# CC-S02-V00-HighSideOutputs.net
KiCad netlist of a schematic drawn in Altium Designer
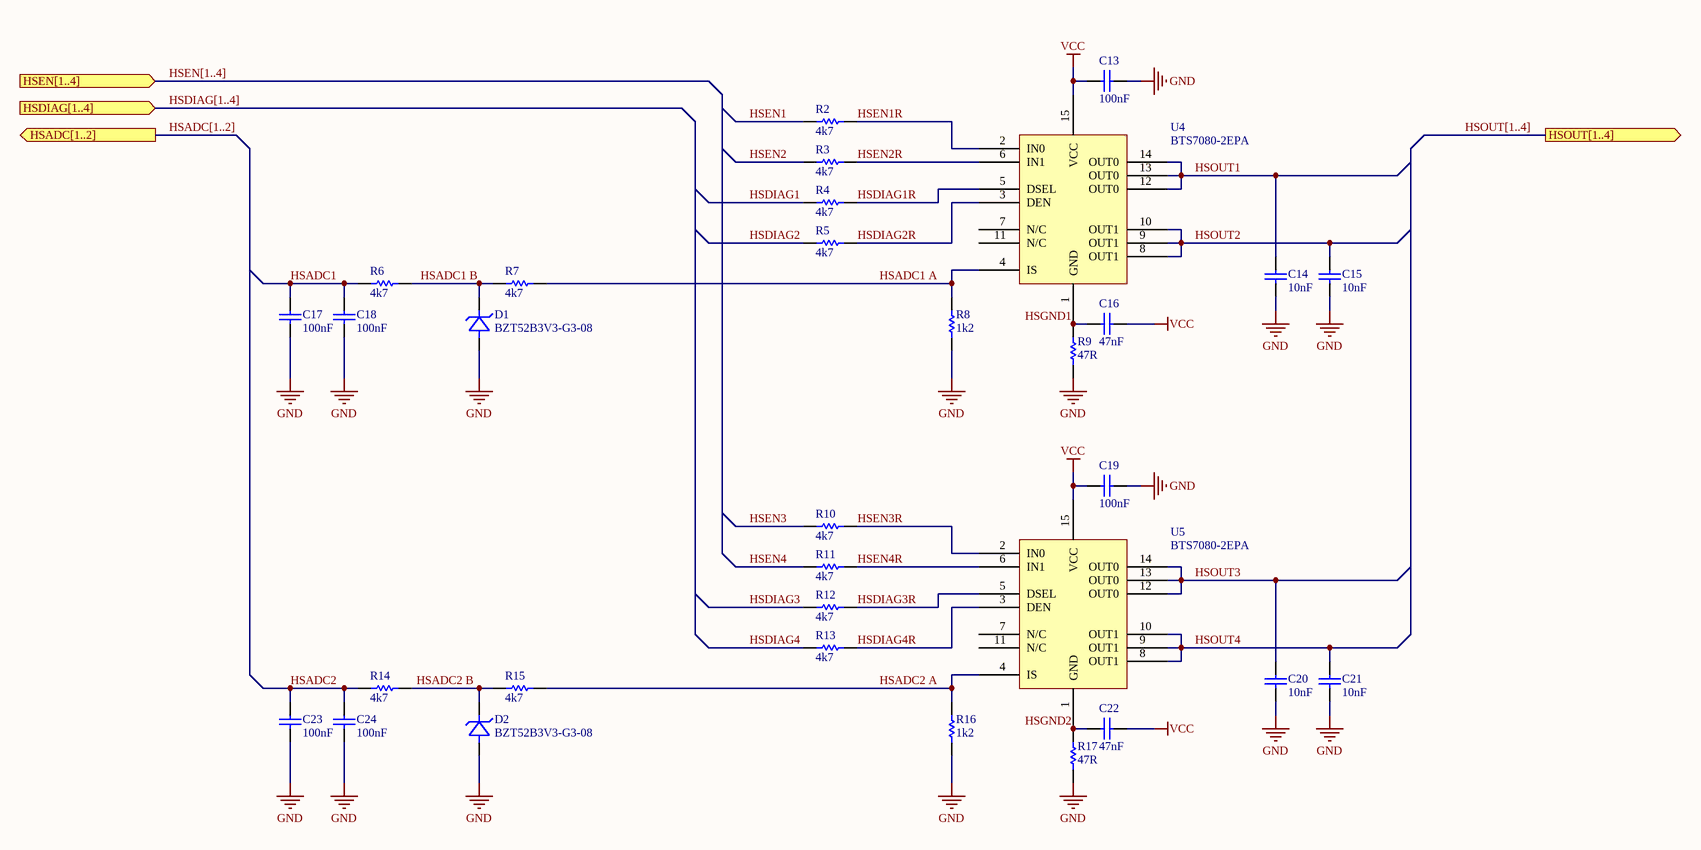
[diagram p0: CC-S02-V00-HighSideOutputs.SchDoc]

(export (version "E")
  (design (tool "Eeschema 10.0.6"))
  (components
    (comp (ref "C13")
      (value "100nF")
      (footprint "Cap_Ceramic_0603")
      (description "Capacitor, Ceramic, SMD, 100nF, 50V, 5%, X7R, 0603")
      (libsource (lib "StandardCapacitors") (part "100nF 50V 5% X7R 0603"))
    )
    (comp (ref "C14")
      (value "10nF")
      (footprint "Cap_Ceramic_0603")
      (description "Capacitor, Ceramic, SMD, 10nF, 50V, 5%, X7R, 0603")
      (libsource (lib "StandardCapacitors") (part "10nF 50V 5% X7R 0603"))
    )
    (comp (ref "C15")
      (value "10nF")
      (footprint "Cap_Ceramic_0603")
      (description "Capacitor, Ceramic, SMD, 10nF, 50V, 5%, X7R, 0603")
      (libsource (lib "StandardCapacitors") (part "10nF 50V 5% X7R 0603"))
    )
    (comp (ref "C16")
      (value "47nF")
      (footprint "Cap_Ceramic_0603")
      (description "Capacitor, Ceramic, SMD, 47nF, 50V, 5%, X7R, 0603")
      (libsource (lib "StandardCapacitors") (part "47nF 50V 5% X7R 0603"))
    )
    (comp (ref "C17")
      (value "100nF")
      (footprint "Cap_Ceramic_0603")
      (description "Capacitor, Ceramic, SMD, 100nF, 50V, 5%, X7R, 0603")
      (libsource (lib "StandardCapacitors") (part "100nF 50V 5% X7R 0603"))
    )
    (comp (ref "C18")
      (value "100nF")
      (footprint "Cap_Ceramic_0603")
      (description "Capacitor, Ceramic, SMD, 100nF, 50V, 5%, X7R, 0603")
      (libsource (lib "StandardCapacitors") (part "100nF 50V 5% X7R 0603"))
    )
    (comp (ref "C19")
      (value "100nF")
      (footprint "Cap_Ceramic_0603")
      (description "Capacitor, Ceramic, SMD, 100nF, 50V, 5%, X7R, 0603")
      (libsource (lib "StandardCapacitors") (part "100nF 50V 5% X7R 0603"))
    )
    (comp (ref "C20")
      (value "10nF")
      (footprint "Cap_Ceramic_0603")
      (description "Capacitor, Ceramic, SMD, 10nF, 50V, 5%, X7R, 0603")
      (libsource (lib "StandardCapacitors") (part "10nF 50V 5% X7R 0603"))
    )
    (comp (ref "C21")
      (value "10nF")
      (footprint "Cap_Ceramic_0603")
      (description "Capacitor, Ceramic, SMD, 10nF, 50V, 5%, X7R, 0603")
      (libsource (lib "StandardCapacitors") (part "10nF 50V 5% X7R 0603"))
    )
    (comp (ref "C22")
      (value "47nF")
      (footprint "Cap_Ceramic_0603")
      (description "Capacitor, Ceramic, SMD, 47nF, 50V, 5%, X7R, 0603")
      (libsource (lib "StandardCapacitors") (part "47nF 50V 5% X7R 0603"))
    )
    (comp (ref "C23")
      (value "100nF")
      (footprint "Cap_Ceramic_0603")
      (description "Capacitor, Ceramic, SMD, 100nF, 50V, 5%, X7R, 0603")
      (libsource (lib "StandardCapacitors") (part "100nF 50V 5% X7R 0603"))
    )
    (comp (ref "C24")
      (value "100nF")
      (footprint "Cap_Ceramic_0603")
      (description "Capacitor, Ceramic, SMD, 100nF, 50V, 5%, X7R, 0603")
      (libsource (lib "StandardCapacitors") (part "100nF 50V 5% X7R 0603"))
    )
    (comp (ref "D1")
      (value "BZT52B3V3-G3-08")
      (footprint "SOD123")
      (description "Diode, SMD, Zenner, 3.3V, 2%, 410mW, SOD-123")
      (libsource (lib "QUTMS_DiodeLibrary") (part "BZT52B3V3-G3-08"))
    )
    (comp (ref "D2")
      (value "BZT52B3V3-G3-08")
      (footprint "SOD123")
      (description "Diode, SMD, Zenner, 3.3V, 2%, 410mW, SOD-123")
      (libsource (lib "QUTMS_DiodeLibrary") (part "BZT52B3V3-G3-08"))
    )
    (comp (ref "R2")
      (value "4k7")
      (footprint "Res_ThinFilm_0603")
      (description "Resistor, SMD, 4k7, 0.1W, 5%, 0603")
      (libsource (lib "StandardResistors") (part "4k7 5% 0603"))
    )
    (comp (ref "R3")
      (value "4k7")
      (footprint "Res_ThinFilm_0603")
      (description "Resistor, SMD, 4k7, 0.1W, 5%, 0603")
      (libsource (lib "StandardResistors") (part "4k7 5% 0603"))
    )
    (comp (ref "R4")
      (value "4k7")
      (footprint "Res_ThinFilm_0603")
      (description "Resistor, SMD, 4k7, 0.1W, 5%, 0603")
      (libsource (lib "StandardResistors") (part "4k7 5% 0603"))
    )
    (comp (ref "R5")
      (value "4k7")
      (footprint "Res_ThinFilm_0603")
      (description "Resistor, SMD, 4k7, 0.1W, 5%, 0603")
      (libsource (lib "StandardResistors") (part "4k7 5% 0603"))
    )
    (comp (ref "R6")
      (value "4k7")
      (footprint "Res_ThinFilm_0603")
      (description "Resistor, SMD, 4k7, 0.1W, 5%, 0603")
      (libsource (lib "StandardResistors") (part "4k7 5% 0603"))
    )
    (comp (ref "R7")
      (value "4k7")
      (footprint "Res_ThinFilm_0603")
      (description "Resistor, SMD, 4k7, 0.1W, 5%, 0603")
      (libsource (lib "StandardResistors") (part "4k7 5% 0603"))
    )
    (comp (ref "R8")
      (value "1k2")
      (footprint "Res_ThinFilm_0603")
      (description "Resistor, SMD, 1k2, 0.1W, 5%, 0603")
      (libsource (lib "StandardResistors") (part "1k2 5% 0603"))
    )
    (comp (ref "R9")
      (value "47R")
      (footprint "Res_ThinFilm_0603")
      (description "Resistor, SMD, 47R, 0.1W, 5%, 0603")
      (libsource (lib "StandardResistors") (part "47R 5% 0603"))
    )
    (comp (ref "R10")
      (value "4k7")
      (footprint "Res_ThinFilm_0603")
      (description "Resistor, SMD, 4k7, 0.1W, 5%, 0603")
      (libsource (lib "StandardResistors") (part "4k7 5% 0603"))
    )
    (comp (ref "R11")
      (value "4k7")
      (footprint "Res_ThinFilm_0603")
      (description "Resistor, SMD, 4k7, 0.1W, 5%, 0603")
      (libsource (lib "StandardResistors") (part "4k7 5% 0603"))
    )
    (comp (ref "R12")
      (value "4k7")
      (footprint "Res_ThinFilm_0603")
      (description "Resistor, SMD, 4k7, 0.1W, 5%, 0603")
      (libsource (lib "StandardResistors") (part "4k7 5% 0603"))
    )
    (comp (ref "R13")
      (value "4k7")
      (footprint "Res_ThinFilm_0603")
      (description "Resistor, SMD, 4k7, 0.1W, 5%, 0603")
      (libsource (lib "StandardResistors") (part "4k7 5% 0603"))
    )
    (comp (ref "R14")
      (value "4k7")
      (footprint "Res_ThinFilm_0603")
      (description "Resistor, SMD, 4k7, 0.1W, 5%, 0603")
      (libsource (lib "StandardResistors") (part "4k7 5% 0603"))
    )
    (comp (ref "R15")
      (value "4k7")
      (footprint "Res_ThinFilm_0603")
      (description "Resistor, SMD, 4k7, 0.1W, 5%, 0603")
      (libsource (lib "StandardResistors") (part "4k7 5% 0603"))
    )
    (comp (ref "R16")
      (value "1k2")
      (footprint "Res_ThinFilm_0603")
      (description "Resistor, SMD, 1k2, 0.1W, 5%, 0603")
      (libsource (lib "StandardResistors") (part "1k2 5% 0603"))
    )
    (comp (ref "R17")
      (value "47R")
      (footprint "Res_ThinFilm_0603")
      (description "Resistor, SMD, 47R, 0.1W, 5%, 0603")
      (libsource (lib "StandardResistors") (part "47R 5% 0603"))
    )
    (comp (ref "U4")
      (value "BTS7080-2EPA")
      (footprint "BTS70802EPA")
      (description "Power Switch/Driver 1:1 N-Channel 3A PG-TSDSO-14-22")
      (libsource (lib "QUTMS_MOSFETLibrary") (part "BTS7080-2EPA"))
    )
    (comp (ref "U5")
      (value "BTS7080-2EPA")
      (footprint "BTS70802EPA")
      (description "Power Switch/Driver 1:1 N-Channel 3A PG-TSDSO-14-22")
      (libsource (lib "QUTMS_MOSFETLibrary") (part "BTS7080-2EPA"))
    )
  )
  (nets
    (net (code "1") (name "/HSADC1") (class "Default")
      (node (ref "C17") (pin "2") (pinfunction "2_2") (pintype "passive"))
      (node (ref "C18") (pin "2") (pinfunction "2_2") (pintype "passive"))
      (node (ref "R6") (pin "1") (pinfunction "1_1") (pintype "passive"))
    )
    (net (code "2") (name "/HSADC1 A") (class "Default")
      (node (ref "R7") (pin "2") (pinfunction "2_2") (pintype "passive"))
      (node (ref "R8") (pin "1") (pinfunction "1_1") (pintype "passive"))
      (node (ref "U4") (pin "4") (pinfunction "IS_4") (pintype "passive"))
    )
    (net (code "3") (name "/HSADC1 B") (class "Default")
      (node (ref "D1") (pin "K") (pinfunction "Cathode_K") (pintype "passive"))
      (node (ref "R6") (pin "2") (pinfunction "2_2") (pintype "passive"))
      (node (ref "R7") (pin "1") (pinfunction "1_1") (pintype "passive"))
    )
    (net (code "4") (name "/HSADC2") (class "Default")
      (node (ref "C23") (pin "2") (pinfunction "2_2") (pintype "passive"))
      (node (ref "C24") (pin "2") (pinfunction "2_2") (pintype "passive"))
      (node (ref "R14") (pin "1") (pinfunction "1_1") (pintype "passive"))
    )
    (net (code "5") (name "/HSADC2 A") (class "Default")
      (node (ref "R15") (pin "2") (pinfunction "2_2") (pintype "passive"))
      (node (ref "R16") (pin "1") (pinfunction "1_1") (pintype "passive"))
      (node (ref "U5") (pin "4") (pinfunction "IS_4") (pintype "passive"))
    )
    (net (code "6") (name "/HSADC2 B") (class "Default")
      (node (ref "D2") (pin "K") (pinfunction "Cathode_K") (pintype "passive"))
      (node (ref "R14") (pin "2") (pinfunction "2_2") (pintype "passive"))
      (node (ref "R15") (pin "1") (pinfunction "1_1") (pintype "passive"))
    )
    (net (code "8") (name "/HSDIAG1") (class "Default")
      (node (ref "R4") (pin "1") (pinfunction "1_1") (pintype "passive"))
    )
    (net (code "9") (name "/HSDIAG1R") (class "Default")
      (node (ref "R4") (pin "2") (pinfunction "2_2") (pintype "passive"))
      (node (ref "U4") (pin "5") (pinfunction "DSEL_5") (pintype "passive"))
    )
    (net (code "10") (name "/HSDIAG2") (class "Default")
      (node (ref "R5") (pin "1") (pinfunction "1_1") (pintype "passive"))
    )
    (net (code "11") (name "/HSDIAG2R") (class "Default")
      (node (ref "R5") (pin "2") (pinfunction "2_2") (pintype "passive"))
      (node (ref "U4") (pin "3") (pinfunction "DEN_3") (pintype "passive"))
    )
    (net (code "12") (name "/HSDIAG3") (class "Default")
      (node (ref "R12") (pin "1") (pinfunction "1_1") (pintype "passive"))
    )
    (net (code "13") (name "/HSDIAG3R") (class "Default")
      (node (ref "R12") (pin "2") (pinfunction "2_2") (pintype "passive"))
      (node (ref "U5") (pin "5") (pinfunction "DSEL_5") (pintype "passive"))
    )
    (net (code "14") (name "/HSDIAG4") (class "Default")
      (node (ref "R13") (pin "1") (pinfunction "1_1") (pintype "passive"))
    )
    (net (code "15") (name "/HSDIAG4R") (class "Default")
      (node (ref "R13") (pin "2") (pinfunction "2_2") (pintype "passive"))
      (node (ref "U5") (pin "3") (pinfunction "DEN_3") (pintype "passive"))
    )
    (net (code "17") (name "/HSEN1") (class "Default")
      (node (ref "R2") (pin "1") (pinfunction "1_1") (pintype "passive"))
    )
    (net (code "18") (name "/HSEN1R") (class "Default")
      (node (ref "R2") (pin "2") (pinfunction "2_2") (pintype "passive"))
      (node (ref "U4") (pin "2") (pinfunction "IN0_2") (pintype "passive"))
    )
    (net (code "19") (name "/HSEN2") (class "Default")
      (node (ref "R3") (pin "1") (pinfunction "1_1") (pintype "passive"))
    )
    (net (code "20") (name "/HSEN2R") (class "Default")
      (node (ref "R3") (pin "2") (pinfunction "2_2") (pintype "passive"))
      (node (ref "U4") (pin "6") (pinfunction "IN1_6") (pintype "passive"))
    )
    (net (code "21") (name "/HSEN3") (class "Default")
      (node (ref "R10") (pin "1") (pinfunction "1_1") (pintype "passive"))
    )
    (net (code "22") (name "/HSEN3R") (class "Default")
      (node (ref "R10") (pin "2") (pinfunction "2_2") (pintype "passive"))
      (node (ref "U5") (pin "2") (pinfunction "IN0_2") (pintype "passive"))
    )
    (net (code "23") (name "/HSEN4") (class "Default")
      (node (ref "R11") (pin "1") (pinfunction "1_1") (pintype "passive"))
    )
    (net (code "24") (name "/HSEN4R") (class "Default")
      (node (ref "R11") (pin "2") (pinfunction "2_2") (pintype "passive"))
      (node (ref "U5") (pin "6") (pinfunction "IN1_6") (pintype "passive"))
    )
    (net (code "26") (name "/HSGND1") (class "Default")
      (node (ref "C16") (pin "1") (pinfunction "1_1") (pintype "passive"))
      (node (ref "R9") (pin "2") (pinfunction "2_2") (pintype "passive"))
      (node (ref "U4") (pin "1") (pinfunction "GND_1") (pintype "passive"))
    )
    (net (code "27") (name "/HSGND2") (class "Default")
      (node (ref "C22") (pin "1") (pinfunction "1_1") (pintype "passive"))
      (node (ref "R17") (pin "2") (pinfunction "2_2") (pintype "passive"))
      (node (ref "U5") (pin "1") (pinfunction "GND_1") (pintype "passive"))
    )
    (net (code "28") (name "/HSOUT1") (class "Default")
      (node (ref "C14") (pin "2") (pinfunction "2_2") (pintype "passive"))
      (node (ref "U4") (pin "12") (pinfunction "OUT0_12") (pintype "passive"))
      (node (ref "U4") (pin "13") (pinfunction "OUT0_13") (pintype "passive"))
      (node (ref "U4") (pin "14") (pinfunction "OUT0_14") (pintype "passive"))
    )
    (net (code "29") (name "/HSOUT2") (class "Default")
      (node (ref "C15") (pin "2") (pinfunction "2_2") (pintype "passive"))
      (node (ref "U4") (pin "10") (pinfunction "OUT1_10") (pintype "passive"))
      (node (ref "U4") (pin "8") (pinfunction "OUT1_8") (pintype "passive"))
      (node (ref "U4") (pin "9") (pinfunction "OUT1_9") (pintype "passive"))
    )
    (net (code "30") (name "/HSOUT3") (class "Default")
      (node (ref "C20") (pin "2") (pinfunction "2_2") (pintype "passive"))
      (node (ref "U5") (pin "12") (pinfunction "OUT0_12") (pintype "passive"))
      (node (ref "U5") (pin "13") (pinfunction "OUT0_13") (pintype "passive"))
      (node (ref "U5") (pin "14") (pinfunction "OUT0_14") (pintype "passive"))
    )
    (net (code "31") (name "/HSOUT4") (class "Default")
      (node (ref "C21") (pin "2") (pinfunction "2_2") (pintype "passive"))
      (node (ref "U5") (pin "10") (pinfunction "OUT1_10") (pintype "passive"))
      (node (ref "U5") (pin "8") (pinfunction "OUT1_8") (pintype "passive"))
      (node (ref "U5") (pin "9") (pinfunction "OUT1_9") (pintype "passive"))
    )
    (net (code "33") (name "GND") (class "Default")
      (node (ref "C13") (pin "2") (pinfunction "2_2") (pintype "passive"))
      (node (ref "C14") (pin "1") (pinfunction "1_1") (pintype "passive"))
      (node (ref "C15") (pin "1") (pinfunction "1_1") (pintype "passive"))
      (node (ref "C17") (pin "1") (pinfunction "1_1") (pintype "passive"))
      (node (ref "C18") (pin "1") (pinfunction "1_1") (pintype "passive"))
      (node (ref "C19") (pin "2") (pinfunction "2_2") (pintype "passive"))
      (node (ref "C20") (pin "1") (pinfunction "1_1") (pintype "passive"))
      (node (ref "C21") (pin "1") (pinfunction "1_1") (pintype "passive"))
      (node (ref "C23") (pin "1") (pinfunction "1_1") (pintype "passive"))
      (node (ref "C24") (pin "1") (pinfunction "1_1") (pintype "passive"))
      (node (ref "D1") (pin "A") (pinfunction "Anode_A") (pintype "passive"))
      (node (ref "D2") (pin "A") (pinfunction "Anode_A") (pintype "passive"))
      (node (ref "R16") (pin "2") (pinfunction "2_2") (pintype "passive"))
      (node (ref "R17") (pin "1") (pinfunction "1_1") (pintype "passive"))
      (node (ref "R8") (pin "2") (pinfunction "2_2") (pintype "passive"))
      (node (ref "R9") (pin "1") (pinfunction "1_1") (pintype "passive"))
    )
    (net (code "34") (name "VCC") (class "Default")
      (node (ref "C13") (pin "1") (pinfunction "1_1") (pintype "passive"))
      (node (ref "C16") (pin "2") (pinfunction "2_2") (pintype "passive"))
      (node (ref "C19") (pin "1") (pinfunction "1_1") (pintype "passive"))
      (node (ref "C22") (pin "2") (pinfunction "2_2") (pintype "passive"))
      (node (ref "U4") (pin "15") (pinfunction "VCC_15") (pintype "passive"))
      (node (ref "U5") (pin "15") (pinfunction "VCC_15") (pintype "passive"))
    )
    (net (code "35") (name "unconnected-(U4-N{slash}C-Pad7)") (class "Default")
      (node (ref "U4") (pin "7") (pinfunction "N/C_7") (pintype "passive"))
    )
    (net (code "36") (name "unconnected-(U4-N{slash}C-Pad11)") (class "Default")
      (node (ref "U4") (pin "11") (pinfunction "N/C_11") (pintype "passive"))
    )
    (net (code "37") (name "unconnected-(U5-N{slash}C-Pad7)") (class "Default")
      (node (ref "U5") (pin "7") (pinfunction "N/C_7") (pintype "passive"))
    )
    (net (code "38") (name "unconnected-(U5-N{slash}C-Pad11)") (class "Default")
      (node (ref "U5") (pin "11") (pinfunction "N/C_11") (pintype "passive"))
    )
  )
)
